# lis100.net
KiCad netlist of a schematic drawn in EAGLE
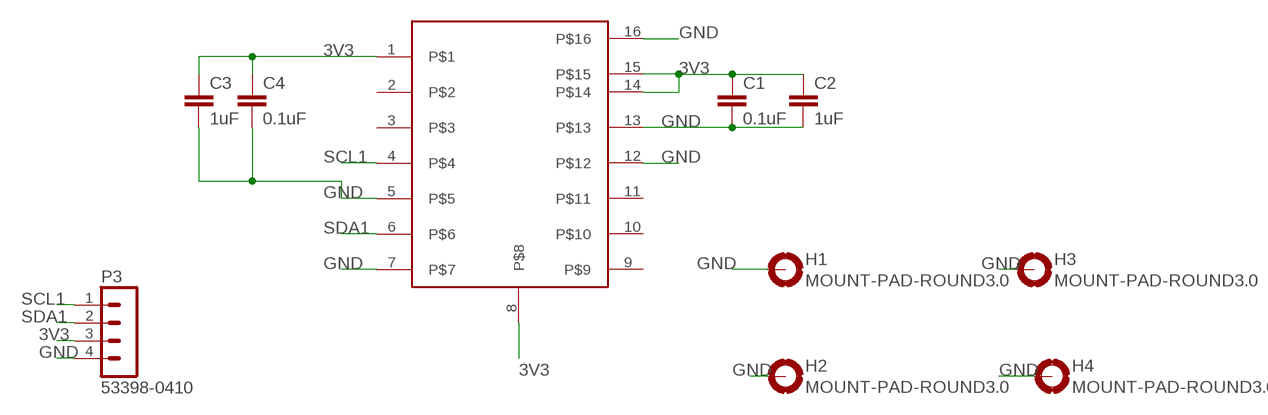
[diagram p0: schematic, sheet 1]

(export (version "E")
  (design (tool "Eeschema 10.0.6"))
  (components
    (comp (ref "C1")
      (value "0.1uF")
      (footprint "eagle-import:C0603")
      (libsource (lib "eagle-import") (part "C-EUC0603"))
    )
    (comp (ref "C2")
      (value "1uF")
      (footprint "eagle-import:C0603")
      (libsource (lib "eagle-import") (part "C-EUC0603"))
    )
    (comp (ref "C3")
      (value "1uF")
      (footprint "eagle-import:C0603")
      (libsource (lib "eagle-import") (part "C-EUC0603"))
    )
    (comp (ref "C4")
      (value "0.1uF")
      (footprint "eagle-import:C0603")
      (libsource (lib "eagle-import") (part "C-EUC0603"))
    )
    (comp (ref "H1")
      (value "MOUNT-PAD-ROUND3.0")
      (footprint "eagle-import:3,0-PAD")
      (libsource (lib "eagle-import") (part "MOUNT-PAD-ROUND3.0"))
    )
    (comp (ref "H2")
      (value "MOUNT-PAD-ROUND3.0")
      (footprint "eagle-import:3,0-PAD")
      (libsource (lib "eagle-import") (part "MOUNT-PAD-ROUND3.0"))
    )
    (comp (ref "H3")
      (value "MOUNT-PAD-ROUND3.0")
      (footprint "eagle-import:3,0-PAD")
      (libsource (lib "eagle-import") (part "MOUNT-PAD-ROUND3.0"))
    )
    (comp (ref "H4")
      (value "MOUNT-PAD-ROUND3.0")
      (footprint "eagle-import:3,0-PAD")
      (libsource (lib "eagle-import") (part "MOUNT-PAD-ROUND3.0"))
    )
    (comp (ref "P3")
      (value "53398-0410")
      (footprint "eagle-import:53398-0410")
      (libsource (lib "eagle-import") (part "53398-0410"))
    )
    (comp (ref "U$1")
      (value "H3LIS100DL")
      (footprint "eagle-import:XDCR_LIS3DHTR")
      (libsource (lib "eagle-import") (part "H3LIS100DL"))
    )
  )
  (nets
    (net (code "1") (name "/3V3") (class "Default")
      (node (ref "C1") (pin "1") (pinfunction "1_1") (pintype "passive"))
      (node (ref "C2") (pin "1") (pinfunction "1_1") (pintype "passive"))
      (node (ref "C3") (pin "1") (pinfunction "1_1") (pintype "passive"))
      (node (ref "C4") (pin "1") (pinfunction "1_1") (pintype "passive"))
      (node (ref "P3") (pin "3") (pinfunction "3_3") (pintype "passive"))
      (node (ref "U$1") (pin "1") (pinfunction "P$1_1") (pintype "bidirectional"))
      (node (ref "U$1") (pin "14") (pinfunction "P$14_14") (pintype "bidirectional"))
      (node (ref "U$1") (pin "15") (pinfunction "P$15_15") (pintype "bidirectional"))
      (node (ref "U$1") (pin "8") (pinfunction "P$8_8") (pintype "bidirectional"))
    )
    (net (code "2") (name "/GND") (class "Default")
      (node (ref "C1") (pin "2") (pinfunction "2_2") (pintype "passive"))
      (node (ref "C2") (pin "2") (pinfunction "2_2") (pintype "passive"))
      (node (ref "C3") (pin "2") (pinfunction "2_2") (pintype "passive"))
      (node (ref "C4") (pin "2") (pinfunction "2_2") (pintype "passive"))
      (node (ref "H1") (pin "B3,0") (pinfunction "MOUNT_B3,0") (pintype "passive"))
      (node (ref "H2") (pin "B3,0") (pinfunction "MOUNT_B3,0") (pintype "passive"))
      (node (ref "H3") (pin "B3,0") (pinfunction "MOUNT_B3,0") (pintype "passive"))
      (node (ref "H4") (pin "B3,0") (pinfunction "MOUNT_B3,0") (pintype "passive"))
      (node (ref "P3") (pin "4") (pinfunction "4_4") (pintype "passive"))
      (node (ref "U$1") (pin "12") (pinfunction "P$12_12") (pintype "bidirectional"))
      (node (ref "U$1") (pin "13") (pinfunction "P$13_13") (pintype "bidirectional"))
      (node (ref "U$1") (pin "16") (pinfunction "P$16_16") (pintype "bidirectional"))
      (node (ref "U$1") (pin "5") (pinfunction "P$5_5") (pintype "bidirectional"))
      (node (ref "U$1") (pin "7") (pinfunction "P$7_7") (pintype "bidirectional"))
    )
    (net (code "3") (name "/SCL1") (class "Default")
      (node (ref "P3") (pin "1") (pinfunction "1_1") (pintype "passive"))
      (node (ref "U$1") (pin "4") (pinfunction "P$4_4") (pintype "bidirectional"))
    )
    (net (code "4") (name "/SDA1") (class "Default")
      (node (ref "P3") (pin "2") (pinfunction "2_2") (pintype "passive"))
      (node (ref "U$1") (pin "6") (pinfunction "P$6_6") (pintype "bidirectional"))
    )
    (net (code "5") (name "unconnected-(U$1-P$2-Pad2)") (class "Default")
      (node (ref "U$1") (pin "2") (pinfunction "P$2_2") (pintype "bidirectional"))
    )
    (net (code "6") (name "unconnected-(U$1-P$3-Pad3)") (class "Default")
      (node (ref "U$1") (pin "3") (pinfunction "P$3_3") (pintype "bidirectional"))
    )
    (net (code "7") (name "unconnected-(U$1-P$9-Pad9)") (class "Default")
      (node (ref "U$1") (pin "9") (pinfunction "P$9_9") (pintype "bidirectional"))
    )
    (net (code "8") (name "unconnected-(U$1-P$10-Pad10)") (class "Default")
      (node (ref "U$1") (pin "10") (pinfunction "P$10_10") (pintype "bidirectional"))
    )
    (net (code "9") (name "unconnected-(U$1-P$11-Pad11)") (class "Default")
      (node (ref "U$1") (pin "11") (pinfunction "P$11_11") (pintype "bidirectional"))
    )
  )
)
